# mkrzero_RGBLEDmatrixPanel.net
KiCad netlist of a schematic drawn in EAGLE
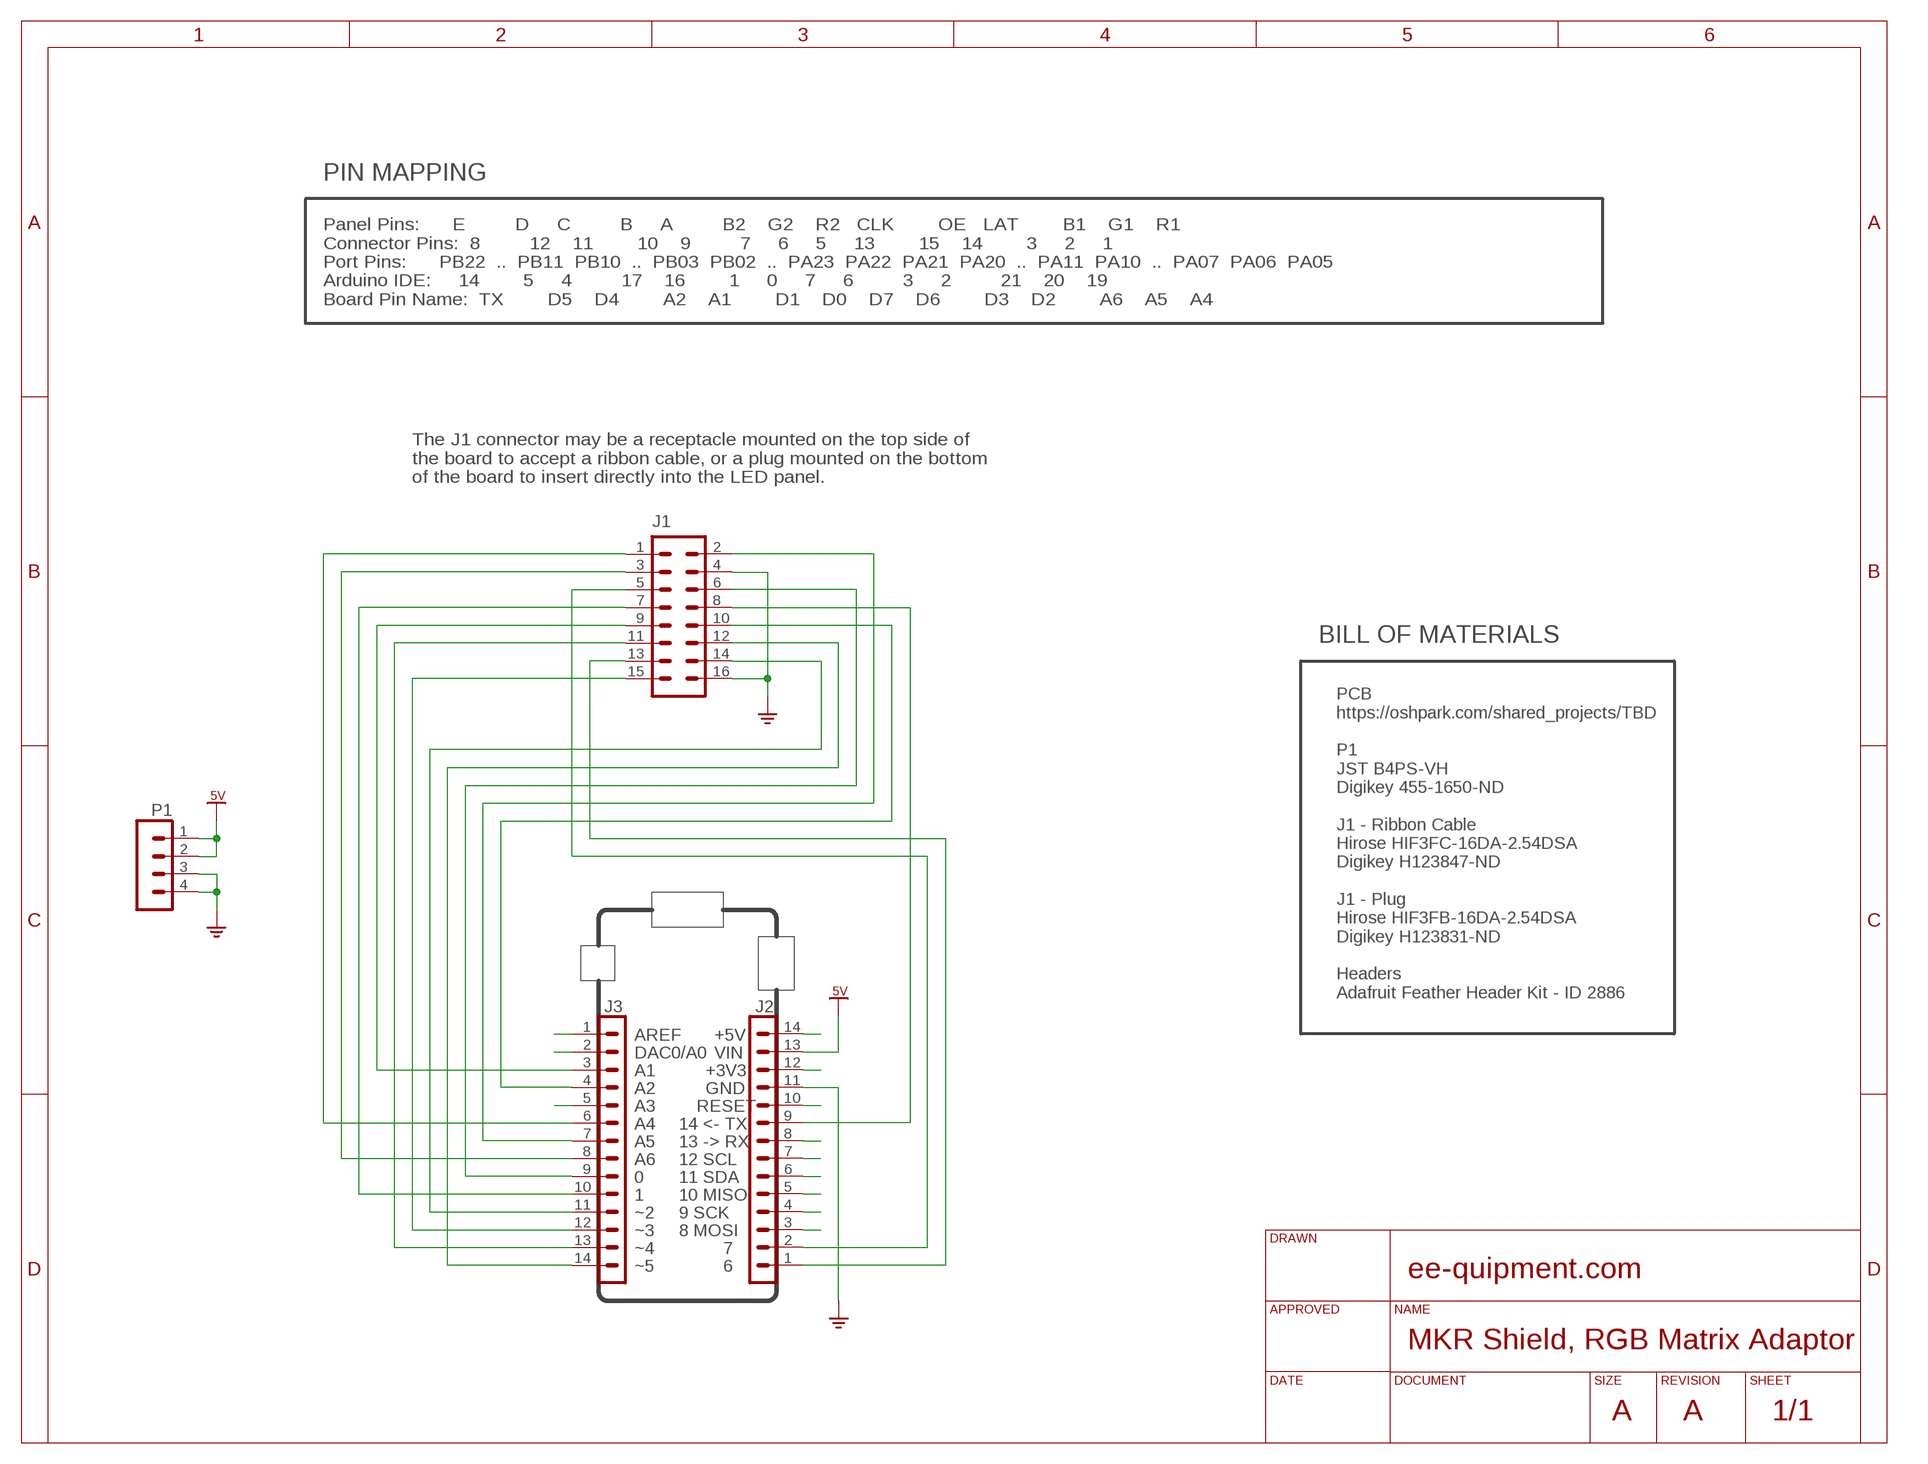
[diagram p0: schematic, sheet 1]

(export (version "E")
  (design (tool "Eeschema 10.0.6"))
  (components
    (comp (ref "J1")
      (value "HDR_16")
      (footprint "eagle-import:HDR_16")
      (libsource (lib "eagle-import") (part "HDR_16"))
    )
    (comp (ref "J2")
      (value "DNP")
      (footprint "eagle-import:STRIP-14-MODULI-A11")
      (libsource (lib "eagle-import") (part "STRIP-14"))
    )
    (comp (ref "J3")
      (value "DNP")
      (footprint "eagle-import:STRIP-14-MODULI-A11")
      (libsource (lib "eagle-import") (part "STRIP-14"))
    )
    (comp (ref "P1")
      (value "JST_B4P-VHRA")
      (footprint "eagle-import:JST_B4PS-VH")
      (libsource (lib "eagle-import") (part "JST_B4P-VHRA"))
    )
  )
  (nets
    (net (code "1") (name "5V") (class "Default")
      (node (ref "J2") (pin "13") (pinfunction "13_13") (pintype "passive"))
      (node (ref "P1") (pin "1") (pinfunction "1_1") (pintype "passive"))
      (node (ref "P1") (pin "2") (pinfunction "2_2") (pintype "passive"))
    )
    (net (code "2") (name "GND") (class "Default")
      (node (ref "J1") (pin "16") (pinfunction "16_16") (pintype "passive"))
      (node (ref "J1") (pin "4") (pinfunction "4_4") (pintype "passive"))
      (node (ref "J2") (pin "11") (pinfunction "11_11") (pintype "passive"))
      (node (ref "P1") (pin "3") (pinfunction "3_3") (pintype "passive"))
      (node (ref "P1") (pin "4") (pinfunction "4_4") (pintype "passive"))
    )
    (net (code "3") (name "Net-(J1-Pad1)") (class "Default")
      (node (ref "J1") (pin "1") (pinfunction "1_1") (pintype "passive"))
      (node (ref "J3") (pin "6") (pinfunction "6_6") (pintype "passive"))
    )
    (net (code "4") (name "Net-(J1-Pad2)") (class "Default")
      (node (ref "J1") (pin "2") (pinfunction "2_2") (pintype "passive"))
      (node (ref "J3") (pin "7") (pinfunction "7_7") (pintype "passive"))
    )
    (net (code "5") (name "Net-(J1-Pad3)") (class "Default")
      (node (ref "J1") (pin "3") (pinfunction "3_3") (pintype "passive"))
      (node (ref "J3") (pin "8") (pinfunction "8_8") (pintype "passive"))
    )
    (net (code "6") (name "Net-(J1-Pad5)") (class "Default")
      (node (ref "J1") (pin "5") (pinfunction "5_5") (pintype "passive"))
      (node (ref "J2") (pin "2") (pinfunction "2_2") (pintype "passive"))
    )
    (net (code "7") (name "Net-(J1-Pad6)") (class "Default")
      (node (ref "J1") (pin "6") (pinfunction "6_6") (pintype "passive"))
      (node (ref "J3") (pin "9") (pinfunction "9_9") (pintype "passive"))
    )
    (net (code "8") (name "Net-(J1-Pad7)") (class "Default")
      (node (ref "J1") (pin "7") (pinfunction "7_7") (pintype "passive"))
      (node (ref "J3") (pin "10") (pinfunction "10_10") (pintype "passive"))
    )
    (net (code "9") (name "Net-(J1-Pad8)") (class "Default")
      (node (ref "J1") (pin "8") (pinfunction "8_8") (pintype "passive"))
      (node (ref "J2") (pin "9") (pinfunction "9_9") (pintype "passive"))
    )
    (net (code "10") (name "Net-(J1-Pad9)") (class "Default")
      (node (ref "J1") (pin "9") (pinfunction "9_9") (pintype "passive"))
      (node (ref "J3") (pin "3") (pinfunction "3_3") (pintype "passive"))
    )
    (net (code "11") (name "Net-(J1-Pad10)") (class "Default")
      (node (ref "J1") (pin "10") (pinfunction "10_10") (pintype "passive"))
      (node (ref "J3") (pin "4") (pinfunction "4_4") (pintype "passive"))
    )
    (net (code "12") (name "Net-(J1-Pad11)") (class "Default")
      (node (ref "J1") (pin "11") (pinfunction "11_11") (pintype "passive"))
      (node (ref "J3") (pin "13") (pinfunction "13_13") (pintype "passive"))
    )
    (net (code "13") (name "Net-(J1-Pad12)") (class "Default")
      (node (ref "J1") (pin "12") (pinfunction "12_12") (pintype "passive"))
      (node (ref "J3") (pin "14") (pinfunction "14_14") (pintype "passive"))
    )
    (net (code "14") (name "Net-(J1-Pad13)") (class "Default")
      (node (ref "J1") (pin "13") (pinfunction "13_13") (pintype "passive"))
      (node (ref "J2") (pin "1") (pinfunction "1_1") (pintype "passive"))
    )
    (net (code "15") (name "Net-(J1-Pad14)") (class "Default")
      (node (ref "J1") (pin "14") (pinfunction "14_14") (pintype "passive"))
      (node (ref "J3") (pin "11") (pinfunction "11_11") (pintype "passive"))
    )
    (net (code "16") (name "Net-(J1-Pad15)") (class "Default")
      (node (ref "J1") (pin "15") (pinfunction "15_15") (pintype "passive"))
      (node (ref "J3") (pin "12") (pinfunction "12_12") (pintype "passive"))
    )
    (net (code "17") (name "unconnected-(J2-Pad3)") (class "Default")
      (node (ref "J2") (pin "3") (pinfunction "3_3") (pintype "passive"))
    )
    (net (code "18") (name "unconnected-(J2-Pad4)") (class "Default")
      (node (ref "J2") (pin "4") (pinfunction "4_4") (pintype "passive"))
    )
    (net (code "19") (name "unconnected-(J2-Pad5)") (class "Default")
      (node (ref "J2") (pin "5") (pinfunction "5_5") (pintype "passive"))
    )
    (net (code "20") (name "unconnected-(J2-Pad6)") (class "Default")
      (node (ref "J2") (pin "6") (pinfunction "6_6") (pintype "passive"))
    )
    (net (code "21") (name "unconnected-(J2-Pad7)") (class "Default")
      (node (ref "J2") (pin "7") (pinfunction "7_7") (pintype "passive"))
    )
    (net (code "22") (name "unconnected-(J2-Pad8)") (class "Default")
      (node (ref "J2") (pin "8") (pinfunction "8_8") (pintype "passive"))
    )
    (net (code "23") (name "unconnected-(J2-Pad10)") (class "Default")
      (node (ref "J2") (pin "10") (pinfunction "10_10") (pintype "passive"))
    )
    (net (code "24") (name "unconnected-(J2-Pad12)") (class "Default")
      (node (ref "J2") (pin "12") (pinfunction "12_12") (pintype "passive"))
    )
    (net (code "25") (name "unconnected-(J2-Pad14)") (class "Default")
      (node (ref "J2") (pin "14") (pinfunction "14_14") (pintype "passive"))
    )
    (net (code "26") (name "unconnected-(J3-Pad1)") (class "Default")
      (node (ref "J3") (pin "1") (pinfunction "1_1") (pintype "passive"))
    )
    (net (code "27") (name "unconnected-(J3-Pad2)") (class "Default")
      (node (ref "J3") (pin "2") (pinfunction "2_2") (pintype "passive"))
    )
    (net (code "28") (name "unconnected-(J3-Pad5)") (class "Default")
      (node (ref "J3") (pin "5") (pinfunction "5_5") (pintype "passive"))
    )
  )
)
